# Power.net
KiCad netlist of a schematic drawn in Altium Designer
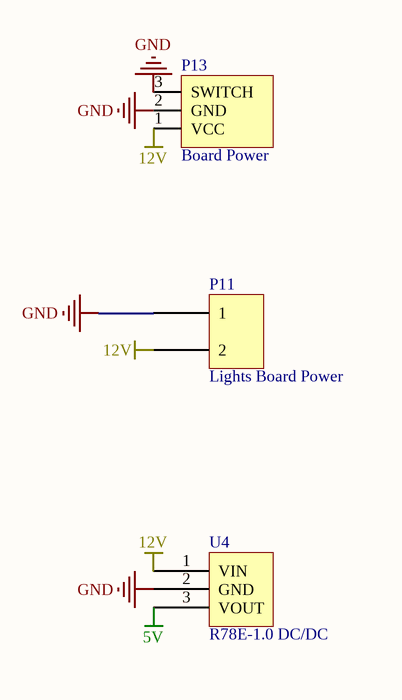
[diagram p0: Power.SchDoc]

(export (version "E")
  (design (tool "Eeschema 10.0.6"))
  (components
    (comp (ref "P11")
      (value "Lights Board Power")
      (footprint "Molex Mini-Fit Jr 2x1")
      (libsource (lib "Molex Mini-Fit Jr 1x2") (part "Molex Mini-Fit 1x2"))
    )
    (comp (ref "P13")
      (value "Board Power")
      (footprint "BARREL JACK PJ007")
      (libsource (lib "BARREL JACK PJ-007") (part "Component_1"))
    )
    (comp (ref "U4")
      (value "R78E-1.0 DC/DC")
      (footprint "R78-1.0")
      (libsource (lib "R78E-1.0_DCDC_SCH") (part "R78E-1.0"))
    )
  )
  (nets
    (net (code "1") (name "5V") (class "Default")
      (node (ref "U4") (pin "3") (pinfunction "VOUT_3") (pintype "passive"))
    )
    (net (code "2") (name "12V") (class "Default")
      (node (ref "P11") (pin "2") (pinfunction "2_2") (pintype "passive"))
      (node (ref "P13") (pin "1") (pinfunction "VCC_1") (pintype "passive"))
      (node (ref "U4") (pin "1") (pinfunction "VIN_1") (pintype "passive"))
    )
    (net (code "3") (name "GND") (class "Default")
      (node (ref "P11") (pin "1") (pinfunction "1_1") (pintype "passive"))
      (node (ref "P13") (pin "2") (pinfunction "GND_2") (pintype "passive"))
      (node (ref "P13") (pin "3") (pinfunction "SWITCH_3") (pintype "passive"))
      (node (ref "U4") (pin "2") (pinfunction "GND_2") (pintype "passive"))
    )
  )
)
